# Main.net
KiCad netlist of a schematic drawn in Altium Designer
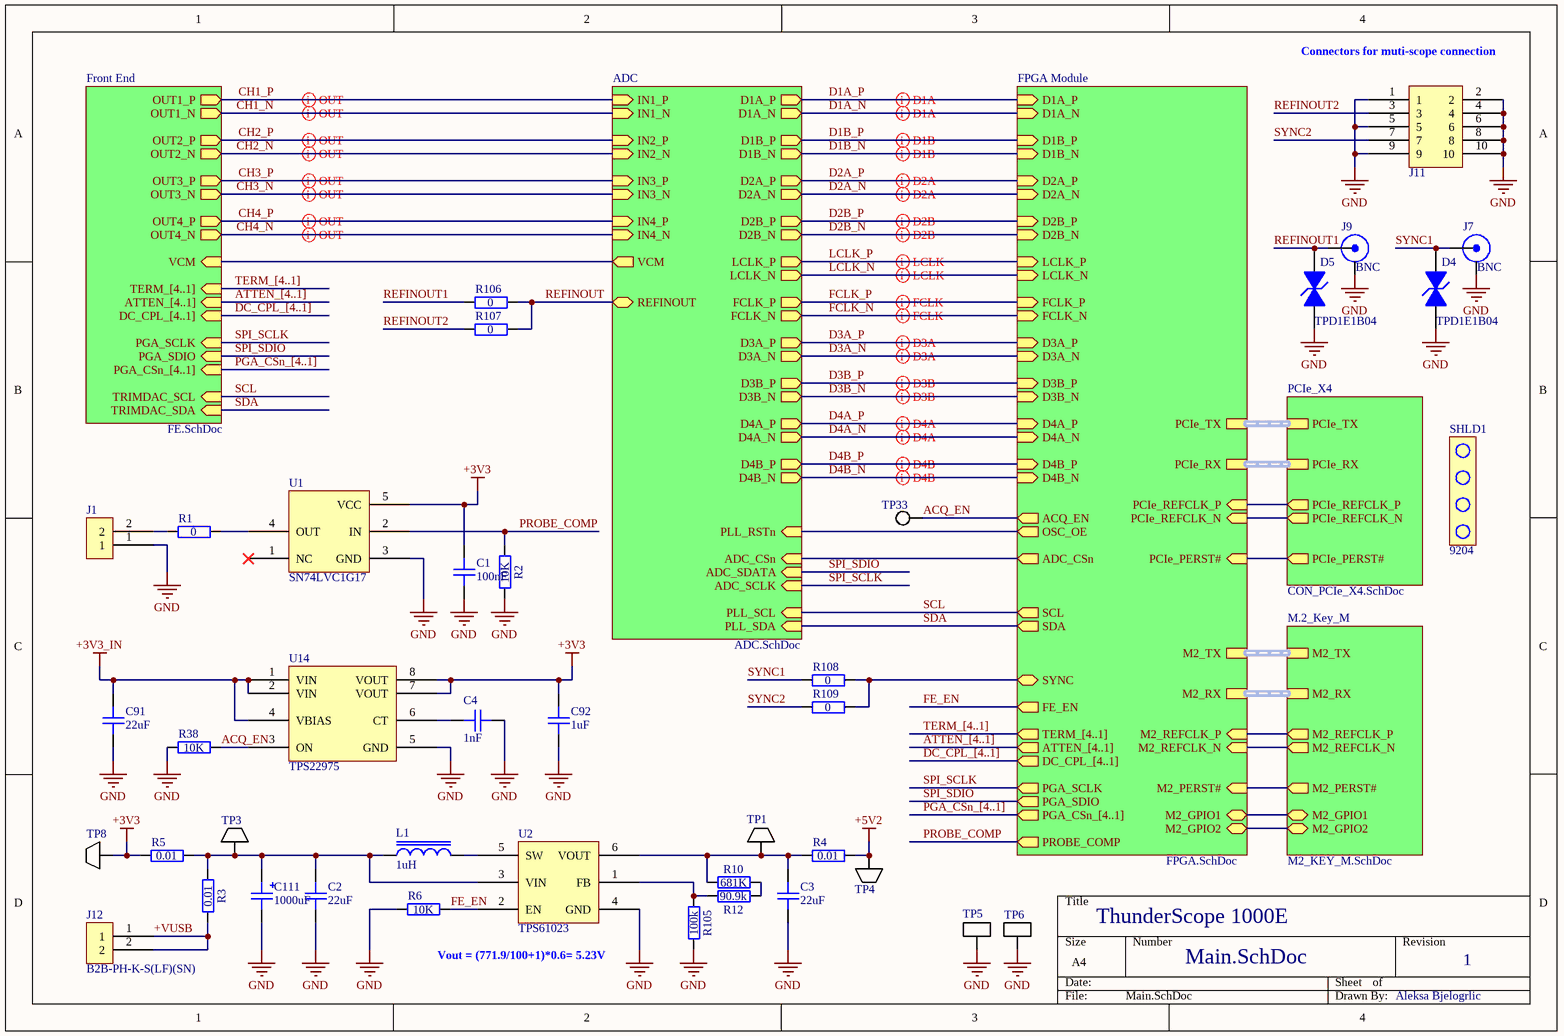
[diagram p0: Main.SchDoc]

(export (version "E")
  (design (tool "Eeschema 10.0.6"))
  (components
    (comp (ref "C1")
      (value "100nF")
      (footprint "GEN_C_0402")
      (libsource (lib "DSO") (part "CAP 100nF 16V X7R 0402"))
    )
    (comp (ref "C2")
      (value "22uF")
      (footprint "GEN_C_0805")
      (libsource (lib "DSO") (part "CAP 22uF 25V X5R 0805"))
    )
    (comp (ref "C3")
      (value "22uF")
      (footprint "GEN_C_0805")
      (libsource (lib "DSO") (part "CAP 22uF 25V X5R 0805"))
    )
    (comp (ref "C4")
      (value "1nF")
      (footprint "GEN_C_0402")
      (libsource (lib "DSO") (part "CAP 1nF 50V C0G 0402"))
    )
    (comp (ref "C91")
      (value "22uF")
      (footprint "GEN_C_0805")
      (libsource (lib "DSO") (part "CAP 22uF 25V X5R 0805"))
    )
    (comp (ref "C92")
      (value "1uF")
      (footprint "GEN_C_0402")
      (libsource (lib "DSO") (part "CAP 1uF 25V X5R 0402"))
    )
    (comp (ref "C111")
      (value "1000uF")
      (footprint "GEN_C_POLAR_10mm")
      (libsource (lib "DSO") (part "CAP 1000uF 16V 10mm Dia"))
    )
    (comp (ref "D4")
      (value "TPD1E1B04")
      (footprint "TI_X1SON_DPY0002A")
      (libsource (lib "DSO") (part "TVS TPD1E1B04"))
    )
    (comp (ref "D5")
      (value "TPD1E1B04")
      (footprint "TI_X1SON_DPY0002A")
      (libsource (lib "DSO") (part "TVS TPD1E1B04"))
    )
    (comp (ref "J1")
      (value "TSW-101-08-F-D-RA")
      (footprint "GEN_2.54mm_1x2_Pin_TH_RA")
      (libsource (lib "DSO") (part "CONN 2.54mm 2 Pin TH RA"))
    )
    (comp (ref "J7") (value "BNC") (footprint "MOL_0731000105") (libsource (lib "DSO") (part "BNC JACK R/A")))
    (comp (ref "J9") (value "BNC") (footprint "MOL_0731000105") (libsource (lib "DSO") (part "BNC JACK R/A")))
    (comp (ref "J11")
      (value "1.27mm 6 Pin TH")
      (footprint "GEN_1.27mm_2x5_Pin_TH_RA")
      (libsource (lib "DSO") (part "CONN 1.27mm 2x5 Pin TH RA"))
    )
    (comp (ref "J12")
      (value "B2B-PH-K-S(LF)(SN)")
      (footprint "JST_B2B-PH-K-S(LF)(SN)")
      (libsource (lib "DSO") (part "CONN JST PH 2 Pin TH"))
    )
    (comp (ref "L1")
      (value "1uH")
      (footprint "GEN_L_1210")
      (libsource (lib "DSO") (part "IND 1uH 3.1A 45 MOHM 1210"))
    )
    (comp (ref "R1")
      (value "0")
      (footprint "GEN_R_0402")
      (libsource (lib "DSO") (part "RES 0 OHM 1/16W 0402"))
    )
    (comp (ref "R2")
      (value "10K")
      (footprint "GEN_R_0402")
      (fields (field (name "TOLERANCE") "1%"))
      (libsource (lib "") (part "RES 10K OHM 1% 1/10W 0402_1"))
    )
    (comp (ref "R3")
      (value "0.01")
      (footprint "GEN_R_0603")
      (fields (field (name "TOLERANCE") "1%"))
      (libsource (lib "DSO") (part "RES 0.01 OHM 1% 1/4W 0603"))
    )
    (comp (ref "R4")
      (value "0.01")
      (footprint "GEN_R_0603")
      (fields (field (name "TOLERANCE") "1%"))
      (libsource (lib "") (part "RES 0.01 OHM 1% 1/4W 0603_2"))
    )
    (comp (ref "R5")
      (value "0.01")
      (footprint "GEN_R_0603")
      (fields (field (name "TOLERANCE") "1%"))
      (libsource (lib "") (part "RES 0.01 OHM 1% 1/4W 0603_1"))
    )
    (comp (ref "R6")
      (value "10K")
      (footprint "GEN_R_0402")
      (fields (field (name "TOLERANCE") "1%"))
      (libsource (lib "DSO") (part "RES 10K OHM 1% 1/10W 0402"))
    )
    (comp (ref "R10")
      (value "681K")
      (footprint "GEN_R_0402")
      (fields (field (name "TOLERANCE") "1%"))
      (libsource (lib "DSO") (part "RES 681K OHM 1% 1/16W 0402"))
    )
    (comp (ref "R12")
      (value "90.9k")
      (footprint "GEN_R_0402")
      (fields (field (name "TOLERANCE") "1%"))
      (libsource (lib "DSO") (part "RES 90.9K OHM 1% 1/16W 0402"))
    )
    (comp (ref "R38")
      (value "10K")
      (footprint "GEN_R_0402")
      (fields (field (name "TOLERANCE") "1%"))
      (libsource (lib "") (part "RES 10K OHM 1% 1/10W 0402_1"))
    )
    (comp (ref "R105")
      (value "100k")
      (footprint "GEN_R_0402")
      (fields (field (name "TOLERANCE") "1%"))
      (libsource (lib "DSO") (part "RES 100K OHM 1% 1/10W 0402"))
    )
    (comp (ref "R106")
      (value "0")
      (footprint "GEN_R_0402")
      (libsource (lib "DSO") (part "RES 0 OHM 1/16W 0402"))
    )
    (comp (ref "R107")
      (value "0")
      (footprint "GEN_R_0402")
      (libsource (lib "DSO") (part "RES 0 OHM 1/16W 0402"))
    )
    (comp (ref "R108")
      (value "0")
      (footprint "GEN_R_0402")
      (libsource (lib "DSO") (part "RES 0 OHM 1/16W 0402"))
    )
    (comp (ref "R109")
      (value "0")
      (footprint "GEN_R_0402")
      (libsource (lib "DSO") (part "RES 0 OHM 1/16W 0402"))
    )
    (comp (ref "SHLD1") (value "9204") (libsource (lib "DSO") (part "PCIe IO Shield")))
    (comp (ref "TP1") (value "5015") (footprint "KEY_5015") (libsource (lib "DSO") (part "TP KEYSTONE 5015")))
    (comp (ref "TP3") (value "5015") (footprint "KEY_5015") (libsource (lib "DSO") (part "TP KEYSTONE 5015")))
    (comp (ref "TP4") (value "5015") (footprint "KEY_5015") (libsource (lib "DSO") (part "TP KEYSTONE 5015")))
    (comp (ref "TP5") (value "5019") (footprint "KEY_5019") (libsource (lib "DSO") (part "TP KEYSTONE 5019")))
    (comp (ref "TP6") (value "5019") (footprint "KEY_5019") (libsource (lib "DSO") (part "TP KEYSTONE 5019")))
    (comp (ref "TP8") (value "5015") (footprint "KEY_5015") (libsource (lib "DSO") (part "TP KEYSTONE 5015")))
    (comp (ref "TP33") (value "PCB") (footprint "GEN_TP_PCB") (libsource (lib "DSO") (part "TP PCB 1mm")))
    (comp (ref "U1")
      (value "SN74LVC1G17")
      (footprint "GEN_SC-70-5")
      (libsource (lib "DSO") (part "IC BUFFER SN74LVC1G17"))
    )
    (comp (ref "U2")
      (value "TPS61023")
      (footprint "TI_SOT563_DRL0006A")
      (libsource (lib "DSO") (part "IC BOOST TPS61023"))
    )
    (comp (ref "U14")
      (value "TPS22975")
      (footprint "TI_WSON8_DSG0008A")
      (libsource (lib "DSO") (part "IC SWITCH LOAD TPS22975"))
    )
  )
  (nets
    (net (code "17") (name "+3V3") (class "Default")
      (node (ref "C1") (pin "1") (pinfunction "1_1") (pintype "passive"))
      (node (ref "C92") (pin "2") (pinfunction "2_2") (pintype "passive"))
      (node (ref "R5") (pin "2") (pinfunction "2_2") (pintype "passive"))
      (node (ref "TP8") (pin "1") (pinfunction "1_1") (pintype "passive"))
      (node (ref "U1") (pin "5") (pinfunction "VCC_5") (pintype "passive"))
      (node (ref "U14") (pin "7") (pinfunction "VOUT_7") (pintype "passive"))
      (node (ref "U14") (pin "8") (pinfunction "VOUT_8") (pintype "passive"))
    )
    (net (code "18") (name "+3V3_IN") (class "Default")
      (node (ref "C91") (pin "2") (pinfunction "2_2") (pintype "passive"))
      (node (ref "U14") (pin "1") (pinfunction "VIN_1") (pintype "passive"))
      (node (ref "U14") (pin "2") (pinfunction "VIN_2") (pintype "passive"))
      (node (ref "U14") (pin "4") (pinfunction "VBIAS_4") (pintype "passive"))
    )
    (net (code "19") (name "+5V2") (class "Default")
      (node (ref "R4") (pin "2") (pinfunction "2_2") (pintype "passive"))
      (node (ref "TP4") (pin "1") (pinfunction "1_1") (pintype "passive"))
    )
    (net (code "20") (name "/+VUSB") (class "Default")
      (node (ref "J12") (pin "1") (pinfunction "1_1") (pintype "passive"))
      (node (ref "J12") (pin "2") (pinfunction "2_2") (pintype "passive"))
      (node (ref "R3") (pin "2") (pinfunction "2_2") (pintype "passive"))
    )
    (net (code "21") (name "/ACQ_EN") (class "Default")
      (node (ref "R38") (pin "2") (pinfunction "2_2") (pintype "passive"))
      (node (ref "TP33") (pin "1") (pinfunction "1_1") (pintype "passive"))
      (node (ref "U14") (pin "3") (pinfunction "ON_3") (pintype "passive"))
    )
    (net (code "51") (name "/FE_EN") (class "Default")
      (node (ref "R6") (pin "1") (pinfunction "1_1") (pintype "passive"))
      (node (ref "U2") (pin "2") (pinfunction "EN_2") (pintype "passive"))
    )
    (net (code "68") (name "/PROBE_COMP") (class "Default")
      (node (ref "R2") (pin "2") (pinfunction "2_2") (pintype "passive"))
      (node (ref "U1") (pin "2") (pinfunction "IN_2") (pintype "passive"))
    )
    (net (code "69") (name "/REFINOUT") (class "Default")
      (node (ref "R106") (pin "2") (pinfunction "2_2") (pintype "passive"))
      (node (ref "R107") (pin "2") (pinfunction "2_2") (pintype "passive"))
    )
    (net (code "70") (name "/REFINOUT1") (class "Default")
      (node (ref "D5") (pin "1") (pinfunction "K_1") (pintype "passive"))
      (node (ref "J9") (pin "1") (pinfunction "Signal_1") (pintype "passive"))
      (node (ref "R106") (pin "1") (pinfunction "1_1") (pintype "passive"))
    )
    (net (code "71") (name "/REFINOUT2") (class "Default")
      (node (ref "J11") (pin "3") (pinfunction "3_3") (pintype "passive"))
      (node (ref "R107") (pin "1") (pinfunction "1_1") (pintype "passive"))
    )
    (net (code "76") (name "/SYNC") (class "Default")
      (node (ref "R108") (pin "2") (pinfunction "2_2") (pintype "passive"))
      (node (ref "R109") (pin "2") (pinfunction "2_2") (pintype "passive"))
    )
    (net (code "77") (name "/SYNC1") (class "Default")
      (node (ref "D4") (pin "1") (pinfunction "K_1") (pintype "passive"))
      (node (ref "J7") (pin "1") (pinfunction "Signal_1") (pintype "passive"))
      (node (ref "R108") (pin "1") (pinfunction "1_1") (pintype "passive"))
    )
    (net (code "78") (name "/SYNC2") (class "Default")
      (node (ref "J11") (pin "7") (pinfunction "7_7") (pintype "passive"))
      (node (ref "R109") (pin "1") (pinfunction "1_1") (pintype "passive"))
    )
    (net (code "81") (name "GND") (class "Default")
      (node (ref "C1") (pin "2") (pinfunction "2_2") (pintype "passive"))
      (node (ref "C111") (pin "2") (pinfunction "2_2") (pintype "passive"))
      (node (ref "C2") (pin "1") (pinfunction "1_1") (pintype "passive"))
      (node (ref "C3") (pin "1") (pinfunction "1_1") (pintype "passive"))
      (node (ref "C4") (pin "1") (pinfunction "1_1") (pintype "passive"))
      (node (ref "C91") (pin "1") (pinfunction "1_1") (pintype "passive"))
      (node (ref "C92") (pin "1") (pinfunction "1_1") (pintype "passive"))
      (node (ref "D4") (pin "2") (pinfunction "A_2") (pintype "passive"))
      (node (ref "D5") (pin "2") (pinfunction "A_2") (pintype "passive"))
      (node (ref "J1") (pin "1") (pinfunction "1_1") (pintype "passive"))
      (node (ref "J11") (pin "1") (pinfunction "1_1") (pintype "passive"))
      (node (ref "J11") (pin "10") (pinfunction "10_10") (pintype "passive"))
      (node (ref "J11") (pin "2") (pinfunction "2_2") (pintype "passive"))
      (node (ref "J11") (pin "4") (pinfunction "4_4") (pintype "passive"))
      (node (ref "J11") (pin "5") (pinfunction "5_5") (pintype "passive"))
      (node (ref "J11") (pin "6") (pinfunction "6_6") (pintype "passive"))
      (node (ref "J11") (pin "8") (pinfunction "8_8") (pintype "passive"))
      (node (ref "J11") (pin "9") (pinfunction "9_9") (pintype "passive"))
      (node (ref "J7") (pin "2") (pinfunction "SHIELD_2") (pintype "passive"))
      (node (ref "J9") (pin "2") (pinfunction "SHIELD_2") (pintype "passive"))
      (node (ref "R105") (pin "1") (pinfunction "1_1") (pintype "passive"))
      (node (ref "R2") (pin "1") (pinfunction "1_1") (pintype "passive"))
      (node (ref "R38") (pin "1") (pinfunction "1_1") (pintype "passive"))
      (node (ref "R6") (pin "2") (pinfunction "2_2") (pintype "passive"))
      (node (ref "TP5") (pin "1") (pinfunction "1_1") (pintype "passive"))
      (node (ref "TP6") (pin "1") (pinfunction "1_1") (pintype "passive"))
      (node (ref "U1") (pin "3") (pinfunction "GND_3") (pintype "passive"))
      (node (ref "U14") (pin "5") (pinfunction "GND_5") (pintype "passive"))
      (node (ref "U2") (pin "4") (pinfunction "GND_4") (pintype "power_in"))
    )
    (net (code "82") (name "Net-(J1-Pad2)") (class "Default")
      (node (ref "J1") (pin "2") (pinfunction "2_2") (pintype "passive"))
      (node (ref "R1") (pin "1") (pinfunction "1_1") (pintype "passive"))
    )
    (net (code "83") (name "Net-(R10-Pad1)") (class "Default")
      (node (ref "R10") (pin "1") (pinfunction "1_1") (pintype "passive"))
      (node (ref "R12") (pin "2") (pinfunction "2_2") (pintype "passive"))
    )
    (net (code "84") (name "Net-(U1-OUT)") (class "Default")
      (node (ref "R1") (pin "2") (pinfunction "2_2") (pintype "passive"))
      (node (ref "U1") (pin "4") (pinfunction "OUT_4") (pintype "passive"))
    )
    (net (code "85") (name "Net-(U2-FB)") (class "Default")
      (node (ref "R105") (pin "2") (pinfunction "2_2") (pintype "passive"))
      (node (ref "R12") (pin "1") (pinfunction "1_1") (pintype "passive"))
      (node (ref "U2") (pin "1") (pinfunction "FB_1") (pintype "passive"))
    )
    (net (code "86") (name "Net-(U2-SW)") (class "Default")
      (node (ref "L1") (pin "2") (pinfunction "2_2") (pintype "passive"))
      (node (ref "U2") (pin "5") (pinfunction "SW_5") (pintype "passive"))
    )
    (net (code "87") (name "Net-(U2-VIN)") (class "Default")
      (node (ref "C111") (pin "1") (pinfunction "1_1") (pintype "passive"))
      (node (ref "C2") (pin "2") (pinfunction "2_2") (pintype "passive"))
      (node (ref "L1") (pin "1") (pinfunction "1_1") (pintype "passive"))
      (node (ref "R3") (pin "1") (pinfunction "1_1") (pintype "passive"))
      (node (ref "R5") (pin "1") (pinfunction "1_1") (pintype "passive"))
      (node (ref "TP3") (pin "1") (pinfunction "1_1") (pintype "passive"))
      (node (ref "U2") (pin "3") (pinfunction "VIN_3") (pintype "power_in"))
    )
    (net (code "88") (name "Net-(U2-VOUT)") (class "Default")
      (node (ref "C3") (pin "2") (pinfunction "2_2") (pintype "passive"))
      (node (ref "R10") (pin "2") (pinfunction "2_2") (pintype "passive"))
      (node (ref "R4") (pin "1") (pinfunction "1_1") (pintype "passive"))
      (node (ref "TP1") (pin "1") (pinfunction "1_1") (pintype "passive"))
      (node (ref "U2") (pin "6") (pinfunction "VOUT_6") (pintype "passive"))
    )
    (net (code "89") (name "Net-(U14-CT)") (class "Default")
      (node (ref "C4") (pin "2") (pinfunction "2_2") (pintype "passive"))
      (node (ref "U14") (pin "6") (pinfunction "CT_6") (pintype "passive"))
    )
    (net (code "90") (name "unconnected-(U1-NC-Pad1)") (class "Default")
      (node (ref "U1") (pin "1") (pinfunction "NC_1") (pintype "passive+no_connect"))
    )
  )
)
